# BootUp.net
KiCad netlist of a schematic drawn in Altium Designer
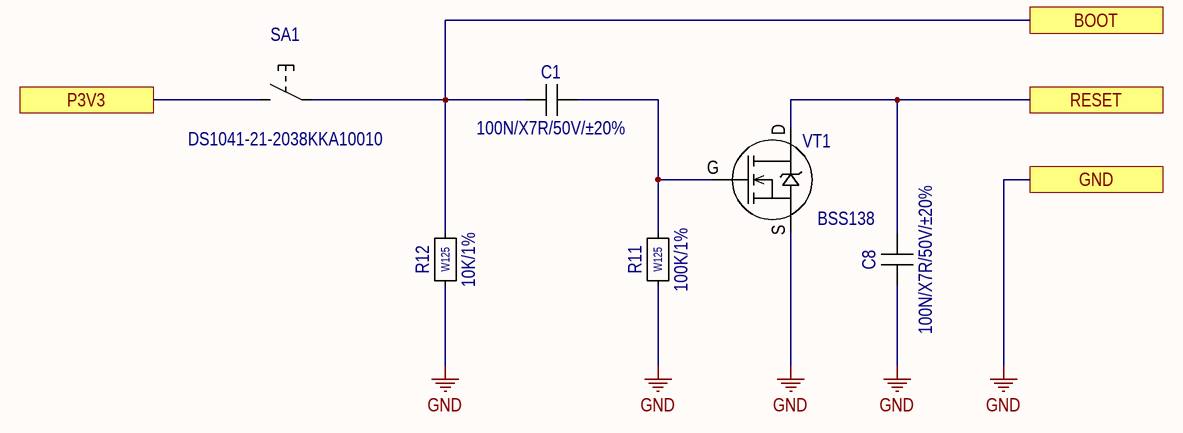
[diagram p0: BootUp.SchDoc]

(export (version "E")
  (design (tool "Eeschema 10.0.6"))
  (components
    (comp (ref "C1")
      (value "100N/X7R/50V/±20%")
      (footprint "Normal_Capacitor_Standard_0805-L2000-W1250-BW500-H1350 - OVERLAY")
      (description "Ceramic Capacitor SMD 0805")
      (fields
        (field (name "MANUFACTURER") "SAMSUNG ELECTRO-MECHANICS")
        (field (name "Comment") "CL21B104MBFNNNE")
      )
      (libsource (lib "Samsung-MLCC-0805") (part "CL21B104MBFNNNE"))
    )
    (comp (ref "C8")
      (value "100N/X7R/50V/±20%")
      (footprint "Normal_Capacitor_Standard_0805-L2000-W1250-BW500-H1350 - OVERLAY")
      (description "Ceramic Capacitor SMD 0805")
      (fields
        (field (name "MANUFACTURER") "SAMSUNG ELECTRO-MECHANICS")
        (field (name "Comment") "CL21B104MBFNNNE")
      )
      (libsource (lib "Samsung-MLCC-0805") (part "CL21B104MBFNNNE"))
    )
    (comp (ref "R11")
      (value "100K/1%")
      (footprint "CHIPRESISTOR-0805-L2000-W1250-B350-H550-Overlay-L4000-W2000")
      (description "Samsung Chip Resistors General Standard 0805")
      (fields
        (field (name "MANUFACTURER") "SAMSUNG ELECTRO-MECHANICS")
        (field (name "Comment") "RC2012(0805)")
      )
      (libsource (lib "Samsung-ChipResistors") (part "RC2012(0805)"))
    )
    (comp (ref "R12")
      (value "10K/1%")
      (footprint "CHIPRESISTOR-0805-L2000-W1250-B350-H550-Overlay-L4000-W2000")
      (description "Samsung Chip Resistors General Standard 0805")
      (fields
        (field (name "MANUFACTURER") "SAMSUNG ELECTRO-MECHANICS")
        (field (name "Comment") "RC2012(0805)")
      )
      (libsource (lib "Samsung-ChipResistors") (part "RC2012(0805)"))
    )
    (comp (ref "SA1")
      (value "DS1041-21-2038KKA10010")
      (footprint "DS1041-21-2038KKA10010")
      (description "6.1x6.1mm Tact Switch R/A 2 Position Type")
      (fields (field (name "MANUFACTURER") "CONNFLY ELECTRONIC CO.,LTD."))
      (libsource (lib "mfmc_components") (part "DS1041-21-2038KKA10010"))
    )
    (comp (ref "VT1")
      (value "BSS138")
      (footprint "3-SOT23 - OVERLAY")
      (libsource (lib "mfmc_components") (part "BSS138"))
    )
  )
  (nets
    (net (code "1") (name "/BOOT") (class "Default")
      (node (ref "C1") (pin "1") (pintype "passive"))
      (node (ref "R12") (pin "2") (pintype "passive"))
      (node (ref "SA1") (pin "1") (pintype "passive"))
    )
    (net (code "2") (name "/P3V3") (class "Default") (node (ref "SA1") (pin "2") (pintype "passive")))
    (net (code "3") (name "/RESET") (class "Default")
      (node (ref "C8") (pin "2") (pintype "passive"))
      (node (ref "VT1") (pin "D") (pintype "passive"))
    )
    (net (code "4") (name "GND") (class "Default")
      (node (ref "C8") (pin "1") (pintype "passive"))
      (node (ref "R11") (pin "1") (pintype "passive"))
      (node (ref "R12") (pin "1") (pintype "passive"))
      (node (ref "VT1") (pin "S") (pintype "passive"))
    )
    (net (code "5") (name "Net-(C1-Pad2)") (class "Default")
      (node (ref "C1") (pin "2") (pintype "passive"))
      (node (ref "R11") (pin "2") (pintype "passive"))
      (node (ref "VT1") (pin "G") (pintype "passive"))
    )
  )
)
